# STM32F4xxR.net
KiCad netlist of a schematic drawn in Altium Designer
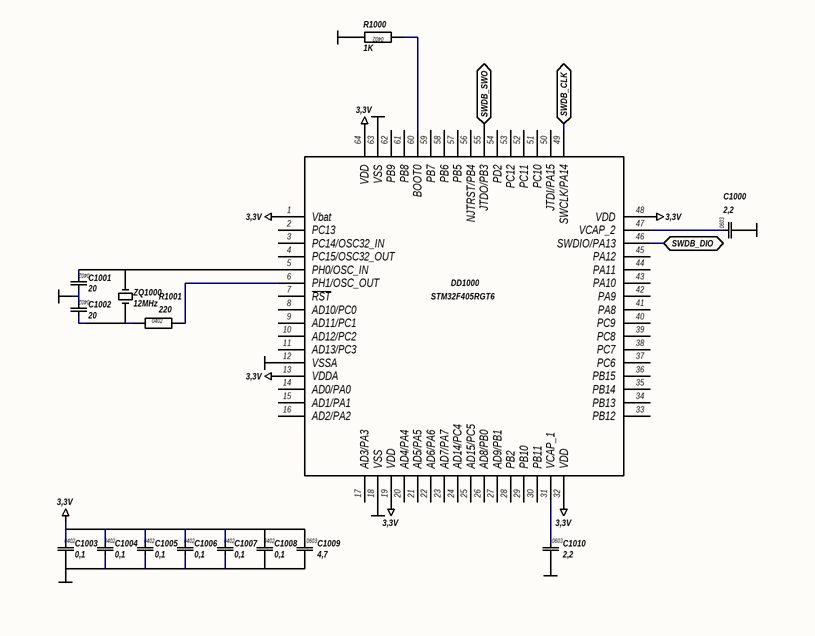
[diagram p0: STM32F4xxR.SchDoc]

(export (version "E")
  (design (tool "Eeschema 10.0.6"))
  (components
    (comp (ref "C1000")
      (value "2,2")
      (footprint "CAP0603")
      (description "Конденсатор чип")
      (libsource (lib "EwgPassive") (part "CAP_0603"))
    )
    (comp (ref "C1001")
      (value "20")
      (footprint "CAP0402")
      (description "Конденсатор чип")
      (libsource (lib "EwgPassive") (part "CAP_0402"))
    )
    (comp (ref "C1002")
      (value "20")
      (footprint "CAP0402")
      (description "Конденсатор чип")
      (libsource (lib "EwgPassive") (part "CAP_0402"))
    )
    (comp (ref "C1003")
      (value "0,1")
      (footprint "CAP0402")
      (description "Конденсатор чип")
      (libsource (lib "EwgPassive") (part "CAP_0402"))
    )
    (comp (ref "C1004")
      (value "0,1")
      (footprint "CAP0402")
      (description "Конденсатор чип")
      (libsource (lib "EwgPassive") (part "CAP_0402"))
    )
    (comp (ref "C1005")
      (value "0,1")
      (footprint "CAP0402")
      (description "Конденсатор чип")
      (libsource (lib "EwgPassive") (part "CAP_0402"))
    )
    (comp (ref "C1006")
      (value "0,1")
      (footprint "CAP0402")
      (description "Конденсатор чип")
      (libsource (lib "EwgPassive") (part "CAP_0402"))
    )
    (comp (ref "C1007")
      (value "0,1")
      (footprint "CAP0402")
      (description "Конденсатор чип")
      (libsource (lib "EwgPassive") (part "CAP_0402"))
    )
    (comp (ref "C1008")
      (value "0,1")
      (footprint "CAP0402")
      (description "Конденсатор чип")
      (libsource (lib "EwgPassive") (part "CAP_0402"))
    )
    (comp (ref "C1009")
      (value "4,7")
      (footprint "CAP0603")
      (description "Конденсатор чип")
      (libsource (lib "EwgPassive") (part "CAP_0603"))
    )
    (comp (ref "C1010")
      (value "2,2")
      (footprint "CAP0603")
      (description "Конденсатор чип")
      (libsource (lib "EwgPassive") (part "CAP_0603"))
    )
    (comp (ref "DD1000")
      (value "STM32F405RGT6")
      (footprint "LQFP64")
      (description "Микроконтроллер")
      (libsource (lib "EwgMicrochips") (part "STM32F4xxR"))
    )
    (comp (ref "R1000")
      (value "1K")
      (footprint "RES0402")
      (description "Резистор чип")
      (libsource (lib "") (part "RES_0402_1"))
    )
    (comp (ref "R1001")
      (value "220")
      (footprint "RES0402")
      (description "Резистор чип")
      (libsource (lib "EwgPassive") (part "RES_0402"))
    )
    (comp (ref "ZQ1000")
      (value "12MHz")
      (footprint "KX-7")
      (description "Кварц")
      (libsource (lib "EwgPassive") (part "KX-7"))
    )
  )
  (nets
    (net (code "1") (name "/SWDB_CLK") (class "Default")
      (node (ref "DD1000") (pin "49") (pinfunction "SWCLK/PA14_49") (pintype "passive"))
    )
    (net (code "2") (name "/SWDB_DIO") (class "Default")
      (node (ref "DD1000") (pin "46") (pinfunction "SWDIO/PA13_46") (pintype "passive"))
    )
    (net (code "3") (name "/SWDB_SWO") (class "Default")
      (node (ref "DD1000") (pin "55") (pinfunction "JTDO/PB3_55") (pintype "passive"))
    )
    (net (code "4") (name "3,3V") (class "Default")
      (node (ref "C1003") (pin "1") (pintype "passive"))
      (node (ref "C1004") (pin "1") (pintype "passive"))
      (node (ref "C1005") (pin "1") (pintype "passive"))
      (node (ref "C1006") (pin "1") (pintype "passive"))
      (node (ref "C1007") (pin "1") (pintype "passive"))
      (node (ref "C1008") (pin "1") (pintype "passive"))
      (node (ref "C1009") (pin "1") (pintype "passive"))
      (node (ref "DD1000") (pin "1") (pinfunction "Vbat_1") (pintype "passive"))
      (node (ref "DD1000") (pin "13") (pinfunction "VDDA_13") (pintype "passive"))
      (node (ref "DD1000") (pin "19") (pinfunction "VDD_19") (pintype "passive"))
      (node (ref "DD1000") (pin "32") (pinfunction "VDD_32") (pintype "passive"))
      (node (ref "DD1000") (pin "48") (pinfunction "VDD_48") (pintype "passive"))
      (node (ref "DD1000") (pin "64") (pinfunction "VDD_64") (pintype "passive"))
    )
    (net (code "5") (name "GND") (class "Default")
      (node (ref "C1000") (pin "2") (pintype "passive"))
      (node (ref "C1001") (pin "2") (pintype "passive"))
      (node (ref "C1002") (pin "1") (pintype "passive"))
      (node (ref "C1003") (pin "2") (pintype "passive"))
      (node (ref "C1004") (pin "2") (pintype "passive"))
      (node (ref "C1005") (pin "2") (pintype "passive"))
      (node (ref "C1006") (pin "2") (pintype "passive"))
      (node (ref "C1007") (pin "2") (pintype "passive"))
      (node (ref "C1008") (pin "2") (pintype "passive"))
      (node (ref "C1009") (pin "2") (pintype "passive"))
      (node (ref "C1010") (pin "2") (pintype "passive"))
      (node (ref "DD1000") (pin "12") (pinfunction "VSSA_12") (pintype "passive"))
      (node (ref "DD1000") (pin "18") (pinfunction "VSS_18") (pintype "passive"))
      (node (ref "DD1000") (pin "63") (pinfunction "VSS_63") (pintype "passive"))
      (node (ref "R1000") (pin "2") (pintype "passive"))
    )
    (net (code "6") (name "Net-(C1002-Pad2)") (class "Default")
      (node (ref "C1002") (pin "2") (pintype "passive"))
      (node (ref "R1001") (pin "1") (pintype "passive"))
      (node (ref "ZQ1000") (pin "3") (pintype "passive"))
    )
    (net (code "7") (name "Net-(DD1000-BOOT0)") (class "Default")
      (node (ref "DD1000") (pin "60") (pinfunction "BOOT0_60") (pintype "passive"))
      (node (ref "R1000") (pin "1") (pintype "passive"))
    )
    (net (code "8") (name "Net-(DD1000-PH0{slash}OSC_IN)") (class "Default")
      (node (ref "C1001") (pin "1") (pintype "passive"))
      (node (ref "DD1000") (pin "5") (pinfunction "PH0/OSC_IN_5") (pintype "passive"))
      (node (ref "ZQ1000") (pin "1") (pintype "passive"))
    )
    (net (code "9") (name "Net-(DD1000-PH1{slash}OSC_OUT)") (class "Default")
      (node (ref "DD1000") (pin "6") (pinfunction "PH1/OSC_OUT_6") (pintype "passive"))
      (node (ref "R1001") (pin "2") (pintype "passive"))
    )
    (net (code "10") (name "Net-(DD1000-VCAP_1)") (class "Default")
      (node (ref "C1010") (pin "1") (pintype "passive"))
      (node (ref "DD1000") (pin "31") (pinfunction "VCAP_1_31") (pintype "passive"))
    )
    (net (code "11") (name "Net-(DD1000-VCAP_2)") (class "Default")
      (node (ref "C1000") (pin "1") (pintype "passive"))
      (node (ref "DD1000") (pin "47") (pinfunction "VCAP_2_47") (pintype "passive"))
    )
    (net (code "12") (name "unconnected-(DD1000-AD0{slash}PA0-Pad14)") (class "Default")
      (node (ref "DD1000") (pin "14") (pinfunction "AD0/PA0_14") (pintype "passive"))
    )
    (net (code "13") (name "unconnected-(DD1000-AD1{slash}PA1-Pad15)") (class "Default")
      (node (ref "DD1000") (pin "15") (pinfunction "AD1/PA1_15") (pintype "passive"))
    )
    (net (code "14") (name "unconnected-(DD1000-AD2{slash}PA2-Pad16)") (class "Default")
      (node (ref "DD1000") (pin "16") (pinfunction "AD2/PA2_16") (pintype "passive"))
    )
    (net (code "15") (name "unconnected-(DD1000-AD3{slash}PA3-Pad17)") (class "Default")
      (node (ref "DD1000") (pin "17") (pinfunction "AD3/PA3_17") (pintype "passive"))
    )
    (net (code "16") (name "unconnected-(DD1000-AD4{slash}PA4-Pad20)") (class "Default")
      (node (ref "DD1000") (pin "20") (pinfunction "AD4/PA4_20") (pintype "passive"))
    )
    (net (code "17") (name "unconnected-(DD1000-AD5{slash}PA5-Pad21)") (class "Default")
      (node (ref "DD1000") (pin "21") (pinfunction "AD5/PA5_21") (pintype "passive"))
    )
    (net (code "18") (name "unconnected-(DD1000-AD6{slash}PA6-Pad22)") (class "Default")
      (node (ref "DD1000") (pin "22") (pinfunction "AD6/PA6_22") (pintype "passive"))
    )
    (net (code "19") (name "unconnected-(DD1000-AD7{slash}PA7-Pad23)") (class "Default")
      (node (ref "DD1000") (pin "23") (pinfunction "AD7/PA7_23") (pintype "passive"))
    )
    (net (code "20") (name "unconnected-(DD1000-AD8{slash}PB0-Pad26)") (class "Default")
      (node (ref "DD1000") (pin "26") (pinfunction "AD8/PB0_26") (pintype "passive"))
    )
    (net (code "21") (name "unconnected-(DD1000-AD9{slash}PB1-Pad27)") (class "Default")
      (node (ref "DD1000") (pin "27") (pinfunction "AD9/PB1_27") (pintype "passive"))
    )
    (net (code "22") (name "unconnected-(DD1000-AD10{slash}PC0-Pad8)") (class "Default")
      (node (ref "DD1000") (pin "8") (pinfunction "AD10/PC0_8") (pintype "passive"))
    )
    (net (code "23") (name "unconnected-(DD1000-AD11{slash}PC1-Pad9)") (class "Default")
      (node (ref "DD1000") (pin "9") (pinfunction "AD11/PC1_9") (pintype "passive"))
    )
    (net (code "24") (name "unconnected-(DD1000-AD12{slash}PC2-Pad10)") (class "Default")
      (node (ref "DD1000") (pin "10") (pinfunction "AD12/PC2_10") (pintype "passive"))
    )
    (net (code "25") (name "unconnected-(DD1000-AD13{slash}PC3-Pad11)") (class "Default")
      (node (ref "DD1000") (pin "11") (pinfunction "AD13/PC3_11") (pintype "passive"))
    )
    (net (code "26") (name "unconnected-(DD1000-AD14{slash}PC4-Pad24)") (class "Default")
      (node (ref "DD1000") (pin "24") (pinfunction "AD14/PC4_24") (pintype "passive"))
    )
    (net (code "27") (name "unconnected-(DD1000-AD15{slash}PC5-Pad25)") (class "Default")
      (node (ref "DD1000") (pin "25") (pinfunction "AD15/PC5_25") (pintype "passive"))
    )
    (net (code "28") (name "unconnected-(DD1000-JTDI{slash}PA15-Pad50)") (class "Default")
      (node (ref "DD1000") (pin "50") (pinfunction "JTDI/PA15_50") (pintype "passive"))
    )
    (net (code "29") (name "unconnected-(DD1000-NJTRST{slash}PB4-Pad56)") (class "Default")
      (node (ref "DD1000") (pin "56") (pinfunction "NJTRST/PB4_56") (pintype "passive"))
    )
    (net (code "30") (name "unconnected-(DD1000-PA8-Pad41)") (class "Default")
      (node (ref "DD1000") (pin "41") (pinfunction "PA8_41") (pintype "passive"))
    )
    (net (code "31") (name "unconnected-(DD1000-PA9-Pad42)") (class "Default")
      (node (ref "DD1000") (pin "42") (pinfunction "PA9_42") (pintype "passive"))
    )
    (net (code "32") (name "unconnected-(DD1000-PA10-Pad43)") (class "Default")
      (node (ref "DD1000") (pin "43") (pinfunction "PA10_43") (pintype "passive"))
    )
    (net (code "33") (name "unconnected-(DD1000-PA11-Pad44)") (class "Default")
      (node (ref "DD1000") (pin "44") (pinfunction "PA11_44") (pintype "passive"))
    )
    (net (code "34") (name "unconnected-(DD1000-PA12-Pad45)") (class "Default")
      (node (ref "DD1000") (pin "45") (pinfunction "PA12_45") (pintype "passive"))
    )
    (net (code "35") (name "unconnected-(DD1000-PB2-Pad28)") (class "Default")
      (node (ref "DD1000") (pin "28") (pinfunction "PB2_28") (pintype "passive"))
    )
    (net (code "36") (name "unconnected-(DD1000-PB5-Pad57)") (class "Default")
      (node (ref "DD1000") (pin "57") (pinfunction "PB5_57") (pintype "passive"))
    )
    (net (code "37") (name "unconnected-(DD1000-PB6-Pad58)") (class "Default")
      (node (ref "DD1000") (pin "58") (pinfunction "PB6_58") (pintype "passive"))
    )
    (net (code "38") (name "unconnected-(DD1000-PB7-Pad59)") (class "Default")
      (node (ref "DD1000") (pin "59") (pinfunction "PB7_59") (pintype "passive"))
    )
    (net (code "39") (name "unconnected-(DD1000-PB8-Pad61)") (class "Default")
      (node (ref "DD1000") (pin "61") (pinfunction "PB8_61") (pintype "passive"))
    )
    (net (code "40") (name "unconnected-(DD1000-PB9-Pad62)") (class "Default")
      (node (ref "DD1000") (pin "62") (pinfunction "PB9_62") (pintype "passive"))
    )
    (net (code "41") (name "unconnected-(DD1000-PB10-Pad29)") (class "Default")
      (node (ref "DD1000") (pin "29") (pinfunction "PB10_29") (pintype "passive"))
    )
    (net (code "42") (name "unconnected-(DD1000-PB11-Pad30)") (class "Default")
      (node (ref "DD1000") (pin "30") (pinfunction "PB11_30") (pintype "passive"))
    )
    (net (code "43") (name "unconnected-(DD1000-PB12-Pad33)") (class "Default")
      (node (ref "DD1000") (pin "33") (pinfunction "PB12_33") (pintype "passive"))
    )
    (net (code "44") (name "unconnected-(DD1000-PB13-Pad34)") (class "Default")
      (node (ref "DD1000") (pin "34") (pinfunction "PB13_34") (pintype "passive"))
    )
    (net (code "45") (name "unconnected-(DD1000-PB14-Pad35)") (class "Default")
      (node (ref "DD1000") (pin "35") (pinfunction "PB14_35") (pintype "passive"))
    )
    (net (code "46") (name "unconnected-(DD1000-PB15-Pad36)") (class "Default")
      (node (ref "DD1000") (pin "36") (pinfunction "PB15_36") (pintype "passive"))
    )
    (net (code "47") (name "unconnected-(DD1000-PC6-Pad37)") (class "Default")
      (node (ref "DD1000") (pin "37") (pinfunction "PC6_37") (pintype "passive"))
    )
    (net (code "48") (name "unconnected-(DD1000-PC7-Pad38)") (class "Default")
      (node (ref "DD1000") (pin "38") (pinfunction "PC7_38") (pintype "passive"))
    )
    (net (code "49") (name "unconnected-(DD1000-PC8-Pad39)") (class "Default")
      (node (ref "DD1000") (pin "39") (pinfunction "PC8_39") (pintype "passive"))
    )
    (net (code "50") (name "unconnected-(DD1000-PC9-Pad40)") (class "Default")
      (node (ref "DD1000") (pin "40") (pinfunction "PC9_40") (pintype "passive"))
    )
    (net (code "51") (name "unconnected-(DD1000-PC10-Pad51)") (class "Default")
      (node (ref "DD1000") (pin "51") (pinfunction "PC10_51") (pintype "passive"))
    )
    (net (code "52") (name "unconnected-(DD1000-PC11-Pad52)") (class "Default")
      (node (ref "DD1000") (pin "52") (pinfunction "PC11_52") (pintype "passive"))
    )
    (net (code "53") (name "unconnected-(DD1000-PC12-Pad53)") (class "Default")
      (node (ref "DD1000") (pin "53") (pinfunction "PC12_53") (pintype "passive"))
    )
    (net (code "54") (name "unconnected-(DD1000-PC13-Pad2)") (class "Default")
      (node (ref "DD1000") (pin "2") (pinfunction "PC13_2") (pintype "passive"))
    )
    (net (code "55") (name "unconnected-(DD1000-PC14{slash}OSC32_IN-Pad3)") (class "Default")
      (node (ref "DD1000") (pin "3") (pinfunction "PC14/OSC32_IN_3") (pintype "passive"))
    )
    (net (code "56") (name "unconnected-(DD1000-PC15{slash}OSC32_OUT-Pad4)") (class "Default")
      (node (ref "DD1000") (pin "4") (pinfunction "PC15/OSC32_OUT_4") (pintype "passive"))
    )
    (net (code "57") (name "unconnected-(DD1000-PD2-Pad54)") (class "Default")
      (node (ref "DD1000") (pin "54") (pinfunction "PD2_54") (pintype "passive"))
    )
    (net (code "58") (name "unconnected-(DD1000-~{RST}-Pad7)") (class "Default")
      (node (ref "DD1000") (pin "7") (pinfunction "~{RST}_7") (pintype "passive"))
    )
    (net (code "59") (name "unconnected-(ZQ1000-Pad2)") (class "Default")
      (node (ref "ZQ1000") (pin "2") (pintype "passive"))
    )
    (net (code "60") (name "unconnected-(ZQ1000-Pad4)") (class "Default")
      (node (ref "ZQ1000") (pin "4") (pintype "passive"))
    )
  )
)
